# The_Breadboard_Version.net
KiCad netlist of a schematic drawn in EAGLE
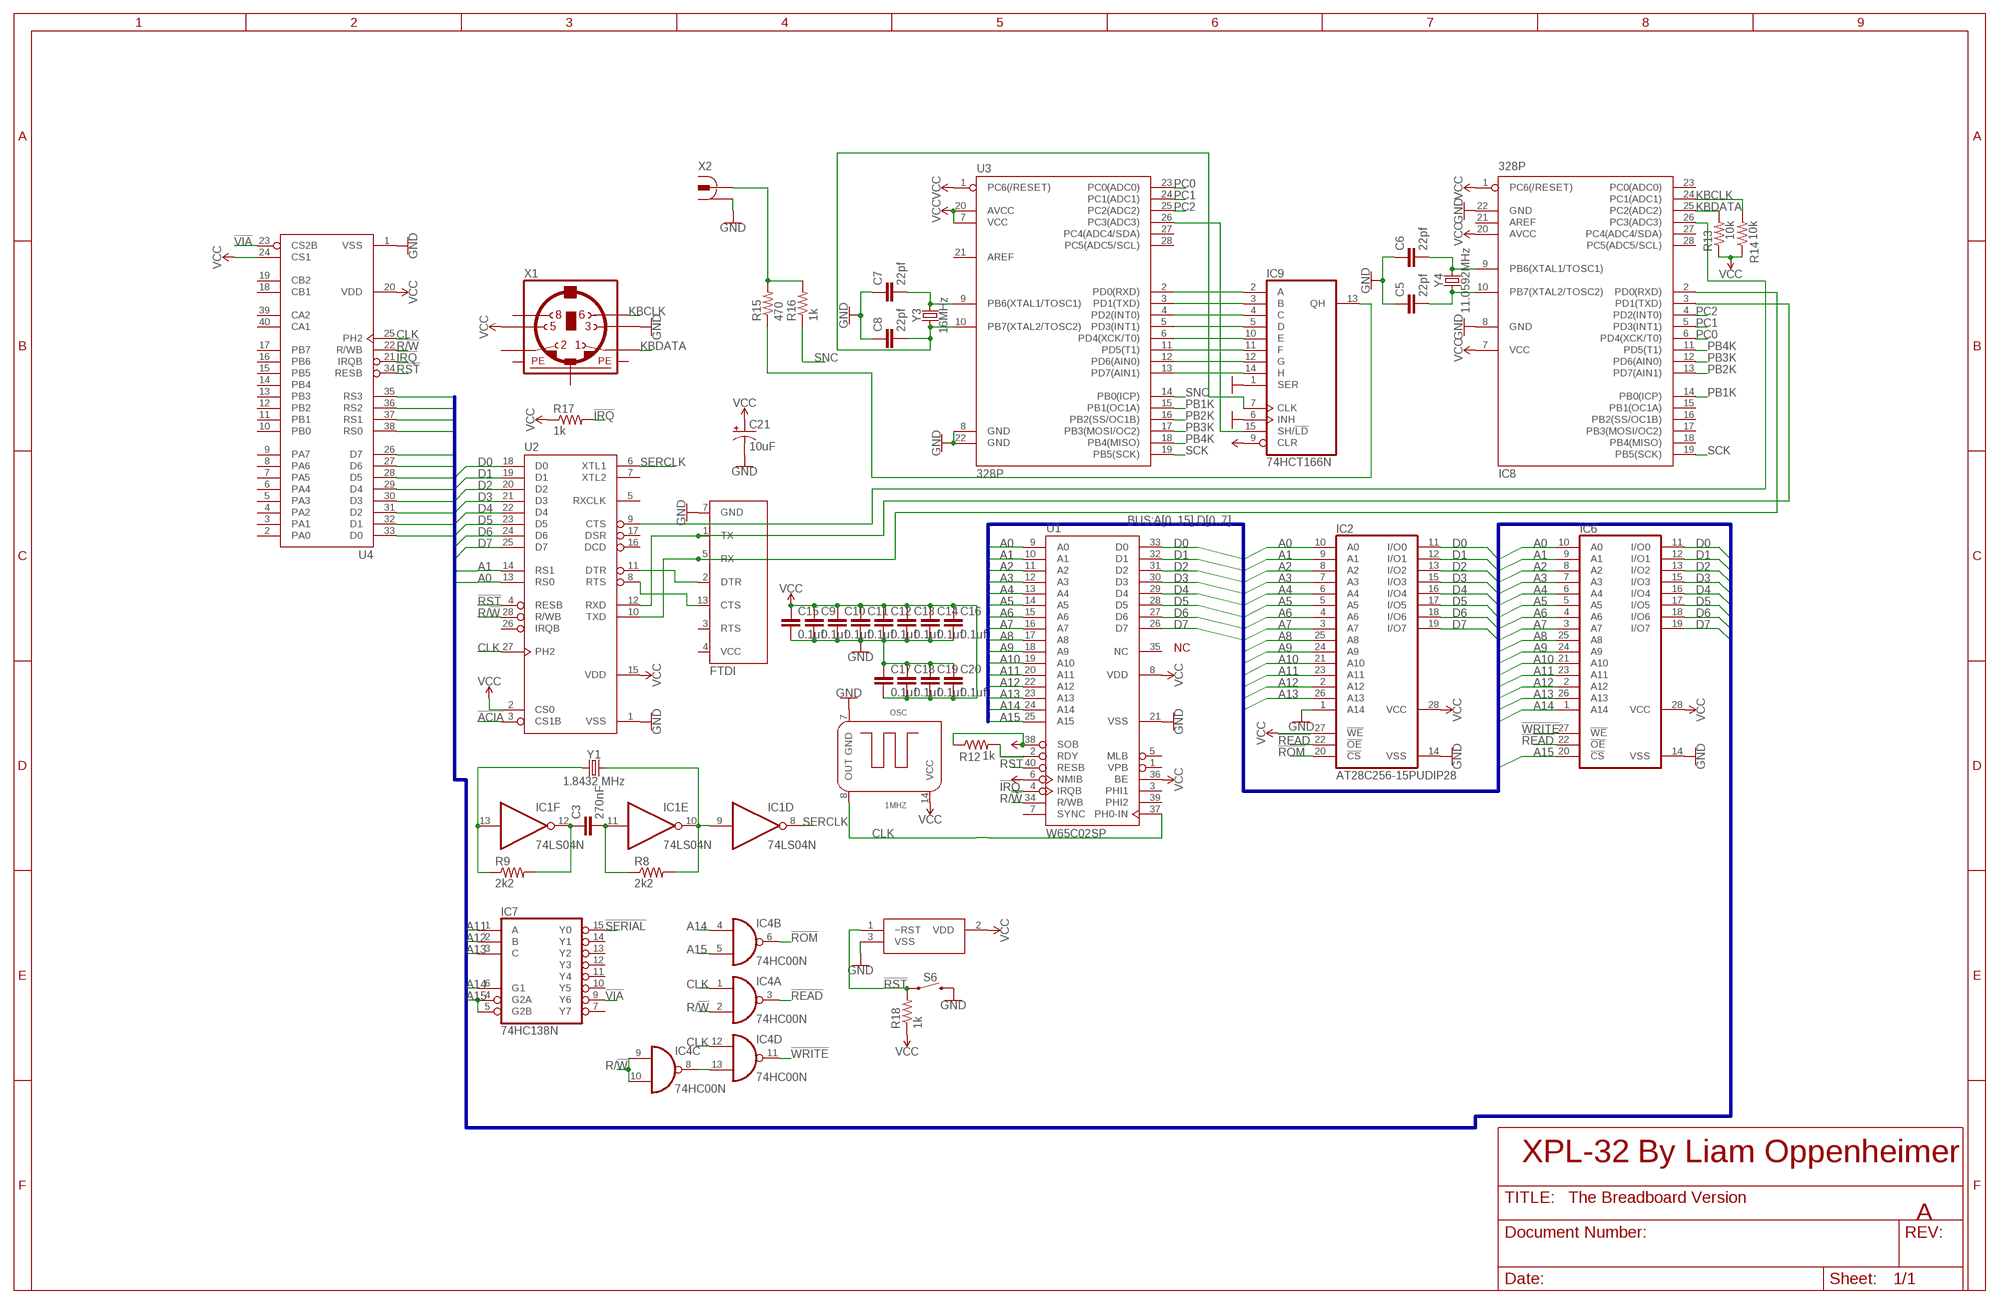
[diagram p0: schematic, sheet 1]

(export (version "E")
  (design (tool "Eeschema 10.0.6"))
  (components
    (comp (ref "1MHZ")
      (value "OSC")
      (footprint "eagle-import:OSCCAN")
      (libsource (lib "eagle-import") (part "OSC"))
    )
    (comp (ref "C3")
      (value "270nF")
      (footprint "eagle-import:C025-025X050")
      (libsource (lib "eagle-import") (part "C-EU025-025X050"))
    )
    (comp (ref "C5")
      (value "22pf")
      (footprint "eagle-import:C025-025X050")
      (libsource (lib "eagle-import") (part "C-EU025-025X050"))
    )
    (comp (ref "C6")
      (value "22pf")
      (footprint "eagle-import:C025-025X050")
      (libsource (lib "eagle-import") (part "C-EU025-025X050"))
    )
    (comp (ref "C7")
      (value "22pf")
      (footprint "eagle-import:C025-025X050")
      (libsource (lib "eagle-import") (part "C-EU025-025X050"))
    )
    (comp (ref "C8")
      (value "22pf")
      (footprint "eagle-import:C025-025X050")
      (libsource (lib "eagle-import") (part "C-EU025-025X050"))
    )
    (comp (ref "C9")
      (value "0.1uf")
      (footprint "eagle-import:C025-025X050")
      (libsource (lib "eagle-import") (part "C-EU025-025X050"))
    )
    (comp (ref "C10")
      (value "0.1uf")
      (footprint "eagle-import:C025-025X050")
      (libsource (lib "eagle-import") (part "C-EU025-025X050"))
    )
    (comp (ref "C11")
      (value "0.1uf")
      (footprint "eagle-import:C025-025X050")
      (libsource (lib "eagle-import") (part "C-EU025-025X050"))
    )
    (comp (ref "C12")
      (value "0.1uf")
      (footprint "eagle-import:C025-025X050")
      (libsource (lib "eagle-import") (part "C-EU025-025X050"))
    )
    (comp (ref "C13")
      (value "0.1uf")
      (footprint "eagle-import:C025-025X050")
      (libsource (lib "eagle-import") (part "C-EU025-025X050"))
    )
    (comp (ref "C14")
      (value "0.1uf")
      (footprint "eagle-import:C025-025X050")
      (libsource (lib "eagle-import") (part "C-EU025-025X050"))
    )
    (comp (ref "C15")
      (value "0.1uf")
      (footprint "eagle-import:C025-025X050")
      (libsource (lib "eagle-import") (part "C-EU025-025X050"))
    )
    (comp (ref "C16")
      (value "0.1uf")
      (footprint "eagle-import:C025-025X050")
      (libsource (lib "eagle-import") (part "C-EU025-025X050"))
    )
    (comp (ref "C17")
      (value "0.1uf")
      (footprint "eagle-import:C025-025X050")
      (libsource (lib "eagle-import") (part "C-EU025-025X050"))
    )
    (comp (ref "C18")
      (value "0.1uf")
      (footprint "eagle-import:C025-025X050")
      (libsource (lib "eagle-import") (part "C-EU025-025X050"))
    )
    (comp (ref "C19")
      (value "0.1uf")
      (footprint "eagle-import:C025-025X050")
      (libsource (lib "eagle-import") (part "C-EU025-025X050"))
    )
    (comp (ref "C20")
      (value "0.1uf")
      (footprint "eagle-import:C025-025X050")
      (libsource (lib "eagle-import") (part "C-EU025-025X050"))
    )
    (comp (ref "C21")
      (value "10uF")
      (footprint "eagle-import:E2,5-7")
      (libsource (lib "eagle-import") (part "CPOL-USE2.5-7"))
    )
    (comp (ref "IC1")
      (value "74LS04N")
      (footprint "eagle-import:DIL14")
      (libsource (lib "eagle-import") (part "7404NLS"))
    )
    (comp (ref "IC2")
      (value "AT28C256-15PUDIP28")
      (footprint "eagle-import:DIP-28")
      (libsource (lib "eagle-import") (part "AT28C256-15PUDIP28"))
    )
    (comp (ref "IC4")
      (value "74HC00N")
      (footprint "eagle-import:DIL14")
      (libsource (lib "eagle-import") (part "7400NHC"))
    )
    (comp (ref "IC6")
      (value "62256P")
      (footprint "eagle-import:DIL28-6")
      (libsource (lib "eagle-import") (part "62256P"))
    )
    (comp (ref "IC7")
      (value "74HC138N")
      (footprint "eagle-import:DIL16")
      (libsource (lib "eagle-import") (part "74138NHC"))
    )
    (comp (ref "IC8")
      (value "328P")
      (footprint "eagle-import:DIL28-3")
      (libsource (lib "eagle-import") (part "MEGA8-P"))
    )
    (comp (ref "IC9")
      (value "74HCT166N")
      (footprint "eagle-import:DIL16")
      (libsource (lib "eagle-import") (part "74166NLS"))
    )
    (comp (ref "IC10")
      (value "MCP120-450DI_TO")
      (footprint "eagle-import:TO127P254X495-3")
      (fields
        (field (name "MANUFACTURER_PART_NUMBER") "MCP120-450DI/TO")
        (field (name "MOUSER_PART_NUMBER") "579-MCP120-450DI/TO")
      )
      (libsource (lib "eagle-import") (part "MCP120-450DI_TO"))
    )
    (comp (ref "R8")
      (value "2k2")
      (footprint "eagle-import:0204_7")
      (libsource (lib "eagle-import") (part "R-US_0204/7"))
    )
    (comp (ref "R9")
      (value "2k2")
      (footprint "eagle-import:0204_7")
      (libsource (lib "eagle-import") (part "R-US_0204/7"))
    )
    (comp (ref "R12")
      (value "1k")
      (footprint "eagle-import:0204_7")
      (libsource (lib "eagle-import") (part "R-US_0204/7"))
    )
    (comp (ref "R13")
      (value "10k")
      (footprint "eagle-import:0204_7")
      (libsource (lib "eagle-import") (part "R-US_0204/7"))
    )
    (comp (ref "R14")
      (value "10k")
      (footprint "eagle-import:0204_7")
      (libsource (lib "eagle-import") (part "R-US_0204/7"))
    )
    (comp (ref "R15")
      (value "470")
      (footprint "eagle-import:0204_7")
      (libsource (lib "eagle-import") (part "R-US_0204/7"))
    )
    (comp (ref "R16")
      (value "1k")
      (footprint "eagle-import:0204_7")
      (libsource (lib "eagle-import") (part "R-US_0204/7"))
    )
    (comp (ref "R17")
      (value "1k")
      (footprint "eagle-import:0204_7")
      (libsource (lib "eagle-import") (part "R-US_0204/7"))
    )
    (comp (ref "R18")
      (value "1k")
      (footprint "eagle-import:0204_7")
      (libsource (lib "eagle-import") (part "R-US_0204/7"))
    )
    (comp (ref "S6")
      (value "MOMENTARY-SWITCH-SPST-PTH-6.0MM")
      (footprint "eagle-import:TACTILE_SWITCH_PTH_6.0MM")
      (libsource (lib "eagle-import") (part "MOMENTARY-SWITCH-SPST-PTH-6.0MM"))
    )
    (comp (ref "U1")
      (value "W65C02SP")
      (footprint "eagle-import:DIP-40")
      (libsource (lib "eagle-import") (part "W65C02SP"))
    )
    (comp (ref "U2")
      (value "G65SC51P")
      (footprint "eagle-import:DIP-28")
      (libsource (lib "eagle-import") (part "G65SC51P"))
    )
    (comp (ref "U3")
      (value "328P")
      (footprint "eagle-import:DIP28")
      (libsource (lib "eagle-import") (part "ATMEGA328P_PDIP"))
    )
    (comp (ref "U4")
      (value "G65SC22P")
      (footprint "eagle-import:DIP-40")
      (libsource (lib "eagle-import") (part "G65SC22P"))
    )
    (comp (ref "U6")
      (value "FTDI")
      (footprint "eagle-import:FTDI")
      (libsource (lib "eagle-import") (part "FTDI"))
    )
    (comp (ref "X1")
      (value "MINI_DIN_6")
      (footprint "eagle-import:M_DIN6")
      (libsource (lib "eagle-import") (part "MINI_DIN_6"))
    )
    (comp (ref "X2")
      (value "736880-49")
      (footprint "eagle-import:736880-49")
      (libsource (lib "eagle-import") (part "736880-49"))
    )
    (comp (ref "Y1")
      (value "1.8432 MHz")
      (footprint "eagle-import:HC49U")
      (libsource (lib "eagle-import") (part "CRYSTALPTH-HC49UV"))
    )
    (comp (ref "Y3")
      (value "16MHz")
      (footprint "eagle-import:HC49U")
      (libsource (lib "eagle-import") (part "CRYSTALPTH-HC49UV"))
    )
    (comp (ref "Y4")
      (value "11.0592MHz")
      (footprint "eagle-import:HC49U")
      (libsource (lib "eagle-import") (part "CRYSTALPTH-HC49UV"))
    )
  )
  (nets
    (net (code "1") (name "/A0") (class "Default")
      (node (ref "IC2") (pin "10") (pinfunction "A0_10") (pintype "input"))
      (node (ref "IC6") (pin "10") (pinfunction "A0_10") (pintype "input"))
      (node (ref "U1") (pin "9") (pinfunction "A0_9") (pintype "bidirectional"))
      (node (ref "U2") (pin "13") (pinfunction "RS0_13") (pintype "input"))
      (node (ref "U4") (pin "38") (pinfunction "RS0_38") (pintype "input"))
    )
    (net (code "2") (name "/A1") (class "Default")
      (node (ref "IC2") (pin "9") (pinfunction "A1_9") (pintype "input"))
      (node (ref "IC6") (pin "9") (pinfunction "A1_9") (pintype "input"))
      (node (ref "U1") (pin "10") (pinfunction "A1_10") (pintype "bidirectional"))
      (node (ref "U2") (pin "14") (pinfunction "RS1_14") (pintype "input"))
      (node (ref "U4") (pin "37") (pinfunction "RS1_37") (pintype "input"))
    )
    (net (code "3") (name "/A2") (class "Default")
      (node (ref "IC2") (pin "8") (pinfunction "A2_8") (pintype "input"))
      (node (ref "IC6") (pin "8") (pinfunction "A2_8") (pintype "input"))
      (node (ref "U1") (pin "11") (pinfunction "A2_11") (pintype "bidirectional"))
      (node (ref "U4") (pin "36") (pinfunction "RS2_36") (pintype "input"))
    )
    (net (code "4") (name "/A3") (class "Default")
      (node (ref "IC2") (pin "7") (pinfunction "A3_7") (pintype "input"))
      (node (ref "IC6") (pin "7") (pinfunction "A3_7") (pintype "input"))
      (node (ref "U1") (pin "12") (pinfunction "A3_12") (pintype "bidirectional"))
      (node (ref "U4") (pin "35") (pinfunction "RS3_35") (pintype "input"))
    )
    (net (code "5") (name "/A4") (class "Default")
      (node (ref "IC2") (pin "6") (pinfunction "A4_6") (pintype "input"))
      (node (ref "IC6") (pin "6") (pinfunction "A4_6") (pintype "input"))
      (node (ref "U1") (pin "13") (pinfunction "A4_13") (pintype "bidirectional"))
    )
    (net (code "6") (name "/A5") (class "Default")
      (node (ref "IC2") (pin "5") (pinfunction "A5_5") (pintype "input"))
      (node (ref "IC6") (pin "5") (pinfunction "A5_5") (pintype "input"))
      (node (ref "U1") (pin "14") (pinfunction "A5_14") (pintype "bidirectional"))
    )
    (net (code "7") (name "/A6") (class "Default")
      (node (ref "IC2") (pin "4") (pinfunction "A6_4") (pintype "input"))
      (node (ref "IC6") (pin "4") (pinfunction "A6_4") (pintype "input"))
      (node (ref "U1") (pin "15") (pinfunction "A6_15") (pintype "bidirectional"))
    )
    (net (code "8") (name "/A7") (class "Default")
      (node (ref "IC2") (pin "3") (pinfunction "A7_3") (pintype "input"))
      (node (ref "IC6") (pin "3") (pinfunction "A7_3") (pintype "input"))
      (node (ref "U1") (pin "16") (pinfunction "A7_16") (pintype "bidirectional"))
    )
    (net (code "9") (name "/A8") (class "Default")
      (node (ref "IC2") (pin "25") (pinfunction "A8_25") (pintype "input"))
      (node (ref "IC6") (pin "25") (pinfunction "A8_25") (pintype "input"))
      (node (ref "U1") (pin "17") (pinfunction "A8_17") (pintype "bidirectional"))
    )
    (net (code "10") (name "/A9") (class "Default")
      (node (ref "IC2") (pin "24") (pinfunction "A9_24") (pintype "input"))
      (node (ref "IC6") (pin "24") (pinfunction "A9_24") (pintype "input"))
      (node (ref "U1") (pin "18") (pinfunction "A9_18") (pintype "bidirectional"))
    )
    (net (code "11") (name "/A10") (class "Default")
      (node (ref "IC2") (pin "21") (pinfunction "A10_21") (pintype "input"))
      (node (ref "IC6") (pin "21") (pinfunction "A10_21") (pintype "input"))
      (node (ref "U1") (pin "19") (pinfunction "A10_19") (pintype "bidirectional"))
    )
    (net (code "12") (name "/A11") (class "Default")
      (node (ref "IC2") (pin "23") (pinfunction "A11_23") (pintype "input"))
      (node (ref "IC6") (pin "23") (pinfunction "A11_23") (pintype "input"))
      (node (ref "IC7") (pin "1") (pinfunction "A_1") (pintype "input"))
      (node (ref "U1") (pin "20") (pinfunction "A11_20") (pintype "bidirectional"))
    )
    (net (code "13") (name "/A12") (class "Default")
      (node (ref "IC2") (pin "2") (pinfunction "A12_2") (pintype "input"))
      (node (ref "IC6") (pin "2") (pinfunction "A12_2") (pintype "input"))
      (node (ref "IC7") (pin "2") (pinfunction "B_2") (pintype "input"))
      (node (ref "U1") (pin "22") (pinfunction "A12_22") (pintype "bidirectional"))
    )
    (net (code "14") (name "/A13") (class "Default")
      (node (ref "IC2") (pin "26") (pinfunction "A13_26") (pintype "input"))
      (node (ref "IC6") (pin "26") (pinfunction "A13_26") (pintype "input"))
      (node (ref "IC7") (pin "3") (pinfunction "C_3") (pintype "input"))
      (node (ref "U1") (pin "23") (pinfunction "A13_23") (pintype "bidirectional"))
    )
    (net (code "15") (name "/A14") (class "Default")
      (node (ref "IC4") (pin "4") (pinfunction "I0_4") (pintype "input"))
      (node (ref "IC6") (pin "1") (pinfunction "A14_1") (pintype "input"))
      (node (ref "IC7") (pin "6") (pinfunction "G1_6") (pintype "input"))
      (node (ref "U1") (pin "24") (pinfunction "A14_24") (pintype "bidirectional"))
    )
    (net (code "16") (name "/A15") (class "Default")
      (node (ref "IC4") (pin "5") (pinfunction "I1_5") (pintype "input"))
      (node (ref "IC6") (pin "20") (pinfunction "~{CS}_20") (pintype "input"))
      (node (ref "IC7") (pin "4") (pinfunction "G2A_4") (pintype "input"))
      (node (ref "IC7") (pin "5") (pinfunction "G2B_5") (pintype "input"))
      (node (ref "U1") (pin "25") (pinfunction "A15_25") (pintype "bidirectional"))
    )
    (net (code "17") (name "/CLK") (class "Default")
      (node (ref "1MHZ") (pin "8") (pinfunction "OUT_8") (pintype "bidirectional"))
      (node (ref "IC4") (pin "1") (pinfunction "I0_1") (pintype "input"))
      (node (ref "IC4") (pin "12") (pinfunction "I0_12") (pintype "input"))
      (node (ref "U1") (pin "37") (pinfunction "PH0-IN_37") (pintype "input"))
      (node (ref "U2") (pin "27") (pinfunction "PH2_27") (pintype "power_in"))
      (node (ref "U4") (pin "25") (pinfunction "PH2_25") (pintype "input"))
    )
    (net (code "18") (name "/D0") (class "Default")
      (node (ref "IC2") (pin "11") (pinfunction "I/O0_11") (pintype "bidirectional"))
      (node (ref "IC6") (pin "11") (pinfunction "I/O0_11") (pintype "bidirectional"))
      (node (ref "U1") (pin "33") (pinfunction "D0_33") (pintype "bidirectional"))
      (node (ref "U2") (pin "18") (pinfunction "D0_18") (pintype "bidirectional"))
      (node (ref "U4") (pin "33") (pinfunction "D0_33") (pintype "bidirectional"))
    )
    (net (code "19") (name "/D1") (class "Default")
      (node (ref "IC2") (pin "12") (pinfunction "I/O1_12") (pintype "bidirectional"))
      (node (ref "IC6") (pin "12") (pinfunction "I/O1_12") (pintype "bidirectional"))
      (node (ref "U1") (pin "32") (pinfunction "D1_32") (pintype "bidirectional"))
      (node (ref "U2") (pin "19") (pinfunction "D1_19") (pintype "bidirectional"))
      (node (ref "U4") (pin "32") (pinfunction "D1_32") (pintype "bidirectional"))
    )
    (net (code "20") (name "/D2") (class "Default")
      (node (ref "IC2") (pin "13") (pinfunction "I/O2_13") (pintype "bidirectional"))
      (node (ref "IC6") (pin "13") (pinfunction "I/O2_13") (pintype "bidirectional"))
      (node (ref "U1") (pin "31") (pinfunction "D2_31") (pintype "bidirectional"))
      (node (ref "U2") (pin "20") (pinfunction "D2_20") (pintype "bidirectional"))
      (node (ref "U4") (pin "31") (pinfunction "D2_31") (pintype "bidirectional"))
    )
    (net (code "21") (name "/D3") (class "Default")
      (node (ref "IC2") (pin "15") (pinfunction "I/O3_15") (pintype "bidirectional"))
      (node (ref "IC6") (pin "15") (pinfunction "I/O3_15") (pintype "bidirectional"))
      (node (ref "U1") (pin "30") (pinfunction "D3_30") (pintype "bidirectional"))
      (node (ref "U2") (pin "21") (pinfunction "D3_21") (pintype "bidirectional"))
      (node (ref "U4") (pin "30") (pinfunction "D3_30") (pintype "bidirectional"))
    )
    (net (code "22") (name "/D4") (class "Default")
      (node (ref "IC2") (pin "16") (pinfunction "I/O4_16") (pintype "bidirectional"))
      (node (ref "IC6") (pin "16") (pinfunction "I/O4_16") (pintype "bidirectional"))
      (node (ref "U1") (pin "29") (pinfunction "D4_29") (pintype "bidirectional"))
      (node (ref "U2") (pin "22") (pinfunction "D4_22") (pintype "bidirectional"))
      (node (ref "U4") (pin "29") (pinfunction "D4_29") (pintype "bidirectional"))
    )
    (net (code "23") (name "/D5") (class "Default")
      (node (ref "IC2") (pin "17") (pinfunction "I/O5_17") (pintype "bidirectional"))
      (node (ref "IC6") (pin "17") (pinfunction "I/O5_17") (pintype "bidirectional"))
      (node (ref "U1") (pin "28") (pinfunction "D5_28") (pintype "bidirectional"))
      (node (ref "U2") (pin "23") (pinfunction "D5_23") (pintype "bidirectional"))
      (node (ref "U4") (pin "28") (pinfunction "D5_28") (pintype "bidirectional"))
    )
    (net (code "24") (name "/D6") (class "Default")
      (node (ref "IC2") (pin "18") (pinfunction "I/O6_18") (pintype "bidirectional"))
      (node (ref "IC6") (pin "18") (pinfunction "I/O6_18") (pintype "bidirectional"))
      (node (ref "U1") (pin "27") (pinfunction "D6_27") (pintype "bidirectional"))
      (node (ref "U2") (pin "24") (pinfunction "D6_24") (pintype "bidirectional"))
      (node (ref "U4") (pin "27") (pinfunction "D6_27") (pintype "bidirectional"))
    )
    (net (code "25") (name "/D7") (class "Default")
      (node (ref "IC2") (pin "19") (pinfunction "I/O7_19") (pintype "bidirectional"))
      (node (ref "IC6") (pin "19") (pinfunction "I/O7_19") (pintype "bidirectional"))
      (node (ref "U1") (pin "26") (pinfunction "D7_26") (pintype "bidirectional"))
      (node (ref "U2") (pin "25") (pinfunction "D7_25") (pintype "bidirectional"))
      (node (ref "U4") (pin "26") (pinfunction "D7_26") (pintype "bidirectional"))
    )
    (net (code "26") (name "/KBCLK") (class "Default")
      (node (ref "IC8") (pin "24") (pinfunction "PC1(ADC1)_24") (pintype "bidirectional"))
      (node (ref "R14") (pin "2") (pinfunction "2_2") (pintype "passive"))
      (node (ref "X1") (pin "6") (pinfunction "6_6") (pintype "passive"))
    )
    (net (code "27") (name "/KBDATA") (class "Default")
      (node (ref "IC8") (pin "25") (pinfunction "PC2(ADC2)_25") (pintype "bidirectional"))
      (node (ref "R13") (pin "2") (pinfunction "2_2") (pintype "passive"))
      (node (ref "X1") (pin "1") (pinfunction "1_1") (pintype "passive"))
    )
    (net (code "28") (name "/PB1K") (class "Default")
      (node (ref "IC8") (pin "14") (pinfunction "PB0(ICP)_14") (pintype "bidirectional"))
      (node (ref "U3") (pin "15") (pinfunction "PB1(OC1A)_15") (pintype "bidirectional"))
    )
    (net (code "29") (name "/PB2K") (class "Default")
      (node (ref "IC8") (pin "13") (pinfunction "PD7(AIN1)_13") (pintype "bidirectional"))
      (node (ref "U3") (pin "16") (pinfunction "PB2(SS/OC1B)_16") (pintype "bidirectional"))
    )
    (net (code "30") (name "/PB3K") (class "Default")
      (node (ref "IC8") (pin "12") (pinfunction "PD6(AIN0)_12") (pintype "bidirectional"))
      (node (ref "U3") (pin "17") (pinfunction "PB3(MOSI/OC2)_17") (pintype "bidirectional"))
    )
    (net (code "31") (name "/PB4K") (class "Default")
      (node (ref "IC8") (pin "11") (pinfunction "PD5(T1)_11") (pintype "bidirectional"))
      (node (ref "U3") (pin "18") (pinfunction "PB4(MISO)_18") (pintype "bidirectional"))
    )
    (net (code "32") (name "/PC0") (class "Default")
      (node (ref "IC8") (pin "6") (pinfunction "PD4(XCK/T0)_6") (pintype "bidirectional"))
      (node (ref "U3") (pin "23") (pinfunction "PC0(ADC0)_23") (pintype "bidirectional"))
    )
    (net (code "33") (name "/PC1") (class "Default")
      (node (ref "IC8") (pin "5") (pinfunction "PD3(INT1)_5") (pintype "bidirectional"))
      (node (ref "U3") (pin "24") (pinfunction "PC1(ADC1)_24") (pintype "bidirectional"))
    )
    (net (code "34") (name "/PC2") (class "Default")
      (node (ref "IC8") (pin "4") (pinfunction "PD2(INT0)_4") (pintype "bidirectional"))
      (node (ref "U3") (pin "25") (pinfunction "PC2(ADC2)_25") (pintype "bidirectional"))
    )
    (net (code "35") (name "/PE1") (class "Default")
      (node (ref "X1") (pin "SH1") (pinfunction "PE1_SH1") (pintype "power_in"))
    )
    (net (code "36") (name "/PE2") (class "Default")
      (node (ref "X1") (pin "SH2") (pinfunction "PE2_SH2") (pintype "power_in"))
    )
    (net (code "37") (name "/PE3") (class "Default")
      (node (ref "X1") (pin "SH3") (pinfunction "PE3_SH3") (pintype "power_in"))
    )
    (net (code "38") (name "/R{slash}~{W}") (class "Default")
      (node (ref "IC4") (pin "10") (pinfunction "I1_10") (pintype "input"))
      (node (ref "IC4") (pin "2") (pinfunction "I1_2") (pintype "input"))
      (node (ref "IC4") (pin "9") (pinfunction "I0_9") (pintype "input"))
      (node (ref "U1") (pin "34") (pinfunction "R/WB_34") (pintype "output"))
      (node (ref "U2") (pin "28") (pinfunction "R/WB_28") (pintype "input"))
      (node (ref "U4") (pin "22") (pinfunction "R/WB_22") (pintype "input"))
    )
    (net (code "39") (name "/SCK") (class "Default")
      (node (ref "IC8") (pin "19") (pinfunction "PB5(SCK)_19") (pintype "bidirectional"))
      (node (ref "U3") (pin "19") (pinfunction "PB5(SCK)_19") (pintype "bidirectional"))
    )
    (net (code "40") (name "/SERCLK") (class "Default")
      (node (ref "IC1") (pin "8") (pinfunction "O_8") (pintype "output"))
      (node (ref "U2") (pin "6") (pinfunction "XTL1_6") (pintype "input"))
    )
    (net (code "41") (name "/SNC") (class "Default")
      (node (ref "R16") (pin "1") (pinfunction "1_1") (pintype "passive"))
      (node (ref "U3") (pin "14") (pinfunction "PB0(ICP)_14") (pintype "bidirectional"))
    )
    (net (code "43") (name "/~{ACIA}") (class "Default")
      (node (ref "U2") (pin "3") (pinfunction "CS1B_3") (pintype "input"))
    )
    (net (code "44") (name "/~{IRQ}") (class "Default")
      (node (ref "R17") (pin "2") (pinfunction "2_2") (pintype "passive"))
      (node (ref "U1") (pin "4") (pinfunction "IRQB_4") (pintype "input"))
      (node (ref "U4") (pin "21") (pinfunction "IRQB_21") (pintype "output"))
    )
    (net (code "45") (name "/~{READ}") (class "Default")
      (node (ref "IC2") (pin "22") (pinfunction "~{OE}_22") (pintype "input"))
      (node (ref "IC4") (pin "3") (pinfunction "O_3") (pintype "output"))
      (node (ref "IC6") (pin "22") (pinfunction "~{OE}_22") (pintype "input"))
    )
    (net (code "46") (name "/~{ROM}") (class "Default")
      (node (ref "IC2") (pin "20") (pinfunction "~{CS}_20") (pintype "input"))
      (node (ref "IC4") (pin "6") (pinfunction "O_6") (pintype "output"))
    )
    (net (code "47") (name "/~{RST}") (class "Default")
      (node (ref "IC10") (pin "1") (pinfunction "~{RST}_1") (pintype "bidirectional"))
      (node (ref "R18") (pin "2") (pinfunction "2_2") (pintype "passive"))
      (node (ref "S6") (pin "1") (pinfunction "1_1") (pintype "passive"))
      (node (ref "U1") (pin "40") (pinfunction "RESB_40") (pintype "input"))
      (node (ref "U2") (pin "4") (pinfunction "RESB_4") (pintype "input"))
      (node (ref "U4") (pin "34") (pinfunction "RESB_34") (pintype "input"))
    )
    (net (code "48") (name "/~{SERIAL}") (class "Default")
      (node (ref "IC7") (pin "15") (pinfunction "Y0_15") (pintype "output"))
    )
    (net (code "49") (name "/~{VIA}") (class "Default")
      (node (ref "IC7") (pin "9") (pinfunction "Y6_9") (pintype "output"))
      (node (ref "U4") (pin "23") (pinfunction "CS2B_23") (pintype "input"))
    )
    (net (code "50") (name "/~{WRITE}") (class "Default")
      (node (ref "IC4") (pin "11") (pinfunction "O_11") (pintype "output"))
      (node (ref "IC6") (pin "27") (pinfunction "~{WE}_27") (pintype "input"))
    )
    (net (code "51") (name "GND") (class "Default")
      (node (ref "1MHZ") (pin "7") (pinfunction "GND_7") (pintype "bidirectional"))
      (node (ref "C10") (pin "2") (pinfunction "2_2") (pintype "passive"))
      (node (ref "C11") (pin "2") (pinfunction "2_2") (pintype "passive"))
      (node (ref "C12") (pin "2") (pinfunction "2_2") (pintype "passive"))
      (node (ref "C13") (pin "2") (pinfunction "2_2") (pintype "passive"))
      (node (ref "C14") (pin "2") (pinfunction "2_2") (pintype "passive"))
      (node (ref "C15") (pin "2") (pinfunction "2_2") (pintype "passive"))
      (node (ref "C16") (pin "2") (pinfunction "2_2") (pintype "passive"))
      (node (ref "C17") (pin "1") (pinfunction "1_1") (pintype "passive"))
      (node (ref "C18") (pin "1") (pinfunction "1_1") (pintype "passive"))
      (node (ref "C19") (pin "1") (pinfunction "1_1") (pintype "passive"))
      (node (ref "C20") (pin "1") (pinfunction "1_1") (pintype "passive"))
      (node (ref "C21") (pin "-") (pinfunction "-_-") (pintype "passive"))
      (node (ref "C5") (pin "1") (pinfunction "1_1") (pintype "passive"))
      (node (ref "C6") (pin "1") (pinfunction "1_1") (pintype "passive"))
      (node (ref "C7") (pin "1") (pinfunction "1_1") (pintype "passive"))
      (node (ref "C8") (pin "1") (pinfunction "1_1") (pintype "passive"))
      (node (ref "C9") (pin "2") (pinfunction "2_2") (pintype "passive"))
      (node (ref "IC10") (pin "3") (pinfunction "VSS_3") (pintype "bidirectional"))
      (node (ref "IC2") (pin "1") (pinfunction "A14_1") (pintype "input"))
      (node (ref "IC2") (pin "14") (pinfunction "VSS_14") (pintype "power_in"))
      (node (ref "IC6") (pin "14") (pinfunction "VSS_14") (pintype "power_in"))
      (node (ref "IC8") (pin "22") (pinfunction "GND_22") (pintype "power_in"))
      (node (ref "IC8") (pin "8") (pinfunction "GND_8") (pintype "power_in"))
      (node (ref "IC9") (pin "1") (pinfunction "SER_1") (pintype "input"))
      (node (ref "IC9") (pin "6") (pinfunction "INH_6") (pintype "input"))
      (node (ref "S6") (pin "3") (pinfunction "2_3") (pintype "passive"))
      (node (ref "U1") (pin "21") (pinfunction "VSS_21") (pintype "power_in"))
      (node (ref "U2") (pin "1") (pinfunction "VSS_1") (pintype "power_in"))
      (node (ref "U3") (pin "22") (pinfunction "GND_22") (pintype "bidirectional"))
      (node (ref "U3") (pin "8") (pinfunction "GND_8") (pintype "bidirectional"))
      (node (ref "U4") (pin "1") (pinfunction "VSS_1") (pintype "power_in"))
      (node (ref "U6") (pin "7") (pinfunction "GND_7") (pintype "bidirectional"))
      (node (ref "X1") (pin "3") (pinfunction "3_3") (pintype "passive"))
      (node (ref "X2") (pin "1") (pinfunction "1_1") (pintype "passive"))
      (node (ref "X2") (pin "1@1") (pinfunction "1_1@1") (pintype "passive"))
      (node (ref "X2") (pin "1@2") (pinfunction "1_1@2") (pintype "passive"))
    )
    (net (code "52") (name "Net-(IC1D-I)") (class "Default")
      (node (ref "IC1") (pin "10") (pinfunction "O_10") (pintype "output"))
      (node (ref "IC1") (pin "9") (pinfunction "I_9") (pintype "input"))
      (node (ref "R8") (pin "2") (pinfunction "2_2") (pintype "passive"))
      (node (ref "Y1") (pin "2") (pinfunction "2_2") (pintype "passive"))
    )
    (net (code "53") (name "Net-(IC1E-I)") (class "Default")
      (node (ref "C3") (pin "2") (pinfunction "2_2") (pintype "passive"))
      (node (ref "IC1") (pin "11") (pinfunction "I_11") (pintype "input"))
      (node (ref "R8") (pin "1") (pinfunction "1_1") (pintype "passive"))
    )
    (net (code "54") (name "Net-(IC1F-I)") (class "Default")
      (node (ref "IC1") (pin "13") (pinfunction "I_13") (pintype "input"))
      (node (ref "R9") (pin "1") (pinfunction "1_1") (pintype "passive"))
      (node (ref "Y1") (pin "1") (pinfunction "1_1") (pintype "passive"))
    )
    (net (code "55") (name "Net-(IC1F-O)") (class "Default")
      (node (ref "C3") (pin "1") (pinfunction "1_1") (pintype "passive"))
      (node (ref "IC1") (pin "12") (pinfunction "O_12") (pintype "output"))
      (node (ref "R9") (pin "2") (pinfunction "2_2") (pintype "passive"))
    )
    (net (code "56") (name "Net-(IC4C-O)") (class "Default")
      (node (ref "IC4") (pin "13") (pinfunction "I1_13") (pintype "input"))
      (node (ref "IC4") (pin "8") (pinfunction "O_8") (pintype "output"))
    )
    (net (code "57") (name "Net-(IC8-PB6(XTAL1{slash}TOSC1))") (class "Default")
      (node (ref "C6") (pin "2") (pinfunction "2_2") (pintype "passive"))
      (node (ref "IC8") (pin "9") (pinfunction "PB6(XTAL1/TOSC1)_9") (pintype "bidirectional"))
      (node (ref "Y4") (pin "2") (pinfunction "2_2") (pintype "passive"))
    )
    (net (code "58") (name "Net-(IC8-PB7(XTAL2{slash}TOSC2))") (class "Default")
      (node (ref "C5") (pin "2") (pinfunction "2_2") (pintype "passive"))
      (node (ref "IC8") (pin "10") (pinfunction "PB7(XTAL2/TOSC2)_10") (pintype "bidirectional"))
      (node (ref "Y4") (pin "1") (pinfunction "1_1") (pintype "passive"))
    )
    (net (code "59") (name "Net-(IC8-PC3(ADC3))") (class "Default")
      (node (ref "IC8") (pin "26") (pinfunction "PC3(ADC3)_26") (pintype "bidirectional"))
      (node (ref "U2") (pin "9") (pinfunction "CTS_9") (pintype "input"))
    )
    (net (code "60") (name "Net-(IC8-PD0(RXD))") (class "Default")
      (node (ref "IC8") (pin "2") (pinfunction "PD0(RXD)_2") (pintype "bidirectional"))
      (node (ref "U2") (pin "10") (pinfunction "TXD_10") (pintype "output"))
      (node (ref "U6") (pin "5") (pinfunction "RX_5") (pintype "bidirectional"))
    )
    (net (code "61") (name "Net-(IC8-PD1(TXD))") (class "Default")
      (node (ref "IC8") (pin "3") (pinfunction "PD1(TXD)_3") (pintype "bidirectional"))
      (node (ref "U2") (pin "12") (pinfunction "RXD_12") (pintype "input"))
      (node (ref "U6") (pin "1") (pinfunction "TX_1") (pintype "bidirectional"))
    )
    (net (code "62") (name "Net-(IC9A-A)") (class "Default")
      (node (ref "IC9") (pin "2") (pinfunction "A_2") (pintype "input"))
      (node (ref "U3") (pin "2") (pinfunction "PD0(RXD)_2") (pintype "bidirectional"))
    )
    (net (code "63") (name "Net-(IC9A-B)") (class "Default")
      (node (ref "IC9") (pin "3") (pinfunction "B_3") (pintype "input"))
      (node (ref "U3") (pin "3") (pinfunction "PD1(TXD)_3") (pintype "bidirectional"))
    )
    (net (code "64") (name "Net-(IC9A-C)") (class "Default")
      (node (ref "IC9") (pin "4") (pinfunction "C_4") (pintype "input"))
      (node (ref "U3") (pin "4") (pinfunction "PD2(INT0)_4") (pintype "bidirectional"))
    )
    (net (code "65") (name "Net-(IC9A-CLK)") (class "Default")
      (node (ref "C8") (pin "2") (pinfunction "2_2") (pintype "passive"))
      (node (ref "IC9") (pin "7") (pinfunction "CLK_7") (pintype "input"))
      (node (ref "U3") (pin "10") (pinfunction "PB7(XTAL2/TOSC2)_10") (pintype "bidirectional"))
      (node (ref "Y3") (pin "1") (pinfunction "1_1") (pintype "passive"))
    )
    (net (code "66") (name "Net-(IC9A-D)") (class "Default")
      (node (ref "IC9") (pin "5") (pinfunction "D_5") (pintype "input"))
      (node (ref "U3") (pin "5") (pinfunction "PD3(INT1)_5") (pintype "bidirectional"))
    )
    (net (code "67") (name "Net-(IC9A-E)") (class "Default")
      (node (ref "IC9") (pin "10") (pinfunction "E_10") (pintype "input"))
      (node (ref "U3") (pin "6") (pinfunction "PD4(XCK/T0)_6") (pintype "bidirectional"))
    )
    (net (code "68") (name "Net-(IC9A-F)") (class "Default")
      (node (ref "IC9") (pin "11") (pinfunction "F_11") (pintype "input"))
      (node (ref "U3") (pin "11") (pinfunction "PD5(T1)_11") (pintype "bidirectional"))
    )
    (net (code "69") (name "Net-(IC9A-G)") (class "Default")
      (node (ref "IC9") (pin "12") (pinfunction "G_12") (pintype "input"))
      (node (ref "U3") (pin "12") (pinfunction "PD6(AIN0)_12") (pintype "bidirectional"))
    )
    (net (code "70") (name "Net-(IC9A-H)") (class "Default")
      (node (ref "IC9") (pin "14") (pinfunction "H_14") (pintype "input"))
      (node (ref "U3") (pin "13") (pinfunction "PD7(AIN1)_13") (pintype "bidirectional"))
    )
    (net (code "71") (name "Net-(IC9A-QH)") (class "Default")
      (node (ref "IC9") (pin "13") (pinfunction "QH_13") (pintype "output"))
      (node (ref "R15") (pin "1") (pinfunction "1_1") (pintype "passive"))
    )
    (net (code "72") (name "Net-(IC9A-SH{slash}~{LD})") (class "Default")
      (node (ref "IC9") (pin "15") (pinfunction "SH/~{LD}_15") (pintype "input"))
      (node (ref "U3") (pin "26") (pinfunction "PC3(ADC3)_26") (pintype "bidirectional"))
    )
    (net (code "73") (name "Net-(R15-Pad2)") (class "Default")
      (node (ref "R15") (pin "2") (pinfunction "2_2") (pintype "passive"))
      (node (ref "R16") (pin "2") (pinfunction "2_2") (pintype "passive"))
      (node (ref "X2") (pin "2") (pinfunction "2_2") (pintype "passive"))
    )
    (net (code "74") (name "Net-(U1-RDY)") (class "Default")
      (node (ref "R12") (pin "2") (pinfunction "2_2") (pintype "passive"))
      (node (ref "U1") (pin "2") (pinfunction "RDY_2") (pintype "bidirectional"))
    )
    (net (code "75") (name "Net-(U2-DTR)") (class "Default")
      (node (ref "U2") (pin "11") (pinfunction "DTR_11") (pintype "output"))
      (node (ref "U6") (pin "2") (pinfunction "DTR_2") (pintype "bidirectional"))
    )
    (net (code "76") (name "Net-(U2-RTS)") (class "Default")
      (node (ref "U2") (pin "8") (pinfunction "RTS_8") (pintype "output"))
      (node (ref "U6") (pin "13") (pinfunction "CTS_13") (pintype "bidirectional"))
    )
    (net (code "77") (name "Net-(U3-PB6(XTAL1{slash}TOSC1))") (class "Default")
      (node (ref "C7") (pin "2") (pinfunction "2_2") (pintype "passive"))
      (node (ref "U3") (pin "9") (pinfunction "PB6(XTAL1/TOSC1)_9") (pintype "bidirectional"))
      (node (ref "Y3") (pin "2") (pinfunction "2_2") (pintype "passive"))
    )
    (net (code "78") (name "VCC") (class "Default")
      (node (ref "1MHZ") (pin "14") (pinfunction "VCC_14") (pintype "bidirectional"))
      (node (ref "C10") (pin "1") (pinfunction "1_1") (pintype "passive"))
      (node (ref "C11") (pin "1") (pinfunction "1_1") (pintype "passive"))
      (node (ref "C12") (pin "1") (pinfunction "1_1") (pintype "passive"))
      (node (ref "C13") (pin "1") (pinfunction "1_1") (pintype "passive"))
      (node (ref "C14") (pin "1") (pinfunction "1_1") (pintype "passive"))
      (node (ref "C15") (pin "1") (pinfunction "1_1") (pintype "passive"))
      (node (ref "C16") (pin "1") (pinfunction "1_1") (pintype "passive"))
      (node (ref "C17") (pin "2") (pinfunction "2_2") (pintype "passive"))
      (node (ref "C18") (pin "2") (pinfunction "2_2") (pintype "passive"))
      (node (ref "C19") (pin "2") (pinfunction "2_2") (pintype "passive"))
      (node (ref "C20") (pin "2") (pinfunction "2_2") (pintype "passive"))
      (node (ref "C21") (pin "+") (pinfunction "+_+") (pintype "passive"))
      (node (ref "C9") (pin "1") (pinfunction "1_1") (pintype "passive"))
      (node (ref "IC10") (pin "2") (pinfunction "VDD_2") (pintype "bidirectional"))
      (node (ref "IC2") (pin "27") (pinfunction "~{WE}_27") (pintype "input"))
      (node (ref "IC2") (pin "28") (pinfunction "VCC_28") (pintype "power_in"))
      (node (ref "IC6") (pin "28") (pinfunction "VCC_28") (pintype "power_in"))
      (node (ref "IC8") (pin "1") (pinfunction "PC6(/RESET)_1") (pintype "bidirectional"))
      (node (ref "IC8") (pin "20") (pinfunction "AVCC_20") (pintype "power_in"))
      (node (ref "IC8") (pin "7") (pinfunction "VCC_7") (pintype "power_in"))
      (node (ref "IC9") (pin "9") (pinfunction "CLR_9") (pintype "input"))
      (node (ref "R12") (pin "1") (pinfunction "1_1") (pintype "passive"))
      (node (ref "R13") (pin "1") (pinfunction "1_1") (pintype "passive"))
      (node (ref "R14") (pin "1") (pinfunction "1_1") (pintype "passive"))
      (node (ref "R17") (pin "1") (pinfunction "1_1") (pintype "passive"))
      (node (ref "R18") (pin "1") (pinfunction "1_1") (pintype "passive"))
      (node (ref "U1") (pin "36") (pinfunction "BE_36") (pintype "input"))
      (node (ref "U1") (pin "38") (pinfunction "SOB_38") (pintype "input"))
      (node (ref "U1") (pin "6") (pinfunction "NMIB_6") (pintype "input"))
      (node (ref "U1") (pin "8") (pinfunction "VDD_8") (pintype "power_in"))
      (node (ref "U2") (pin "15") (pinfunction "VDD_15") (pintype "power_in"))
      (node (ref "U2") (pin "2") (pinfunction "CS0_2") (pintype "input"))
      (node (ref "U3") (pin "1") (pinfunction "PC6(/RESET)_1") (pintype "bidirectional"))
      (node (ref "U3") (pin "20") (pinfunction "AVCC_20") (pintype "bidirectional"))
      (node (ref "U3") (pin "7") (pinfunction "VCC_7") (pintype "bidirectional"))
      (node (ref "U4") (pin "20") (pinfunction "VDD_20") (pintype "power_in"))
      (node (ref "U4") (pin "24") (pinfunction "CS1_24") (pintype "input"))
      (node (ref "X1") (pin "5") (pinfunction "5_5") (pintype "passive"))
    )
    (net (code "79") (name "unconnected-(IC7A-Y1-Pad14)") (class "Default")
      (node (ref "IC7") (pin "14") (pinfunction "Y1_14") (pintype "output"))
    )
    (net (code "80") (name "unconnected-(IC7A-Y2-Pad13)") (class "Default")
      (node (ref "IC7") (pin "13") (pinfunction "Y2_13") (pintype "output"))
    )
    (net (code "81") (name "unconnected-(IC7A-Y3-Pad12)") (class "Default")
      (node (ref "IC7") (pin "12") (pinfunction "Y3_12") (pintype "output"))
    )
    (net (code "82") (name "unconnected-(IC7A-Y4-Pad11)") (class "Default")
      (node (ref "IC7") (pin "11") (pinfunction "Y4_11") (pintype "output"))
    )
    (net (code "83") (name "unconnected-(IC7A-Y5-Pad10)") (class "Default")
      (node (ref "IC7") (pin "10") (pinfunction "Y5_10") (pintype "output"))
    )
    (net (code "84") (name "unconnected-(IC7A-Y7-Pad7)") (class "Default")
      (node (ref "IC7") (pin "7") (pinfunction "Y7_7") (pintype "output"))
    )
    (net (code "85") (name "unconnected-(IC8-AREF-Pad21)") (class "Default")
      (node (ref "IC8") (pin "21") (pinfunction "AREF_21") (pintype "passive"))
    )
    (net (code "86") (name "unconnected-(IC8-PB1(OC1A)-Pad15)") (class "Default")
      (node (ref "IC8") (pin "15") (pinfunction "PB1(OC1A)_15") (pintype "bidirectional"))
    )
    (net (code "87") (name "unconnected-(IC8-PB2(SS{slash}OC1B)-Pad16)") (class "Default")
      (node (ref "IC8") (pin "16") (pinfunction "PB2(SS/OC1B)_16") (pintype "bidirectional"))
    )
    (net (code "88") (name "unconnected-(IC8-PB3(MOSI{slash}OC2)-Pad17)") (class "Default")
      (node (ref "IC8") (pin "17") (pinfunction "PB3(MOSI/OC2)_17") (pintype "bidirectional"))
    )
    (net (code "89") (name "unconnected-(IC8-PB4(MISO)-Pad18)") (class "Default")
      (node (ref "IC8") (pin "18") (pinfunction "PB4(MISO)_18") (pintype "bidirectional"))
    )
    (net (code "90") (name "unconnected-(IC8-PC0(ADC0)-Pad23)") (class "Default")
      (node (ref "IC8") (pin "23") (pinfunction "PC0(ADC0)_23") (pintype "bidirectional"))
    )
    (net (code "91") (name "unconnected-(IC8-PC4(ADC4{slash}SDA)-Pad27)") (class "Default")
      (node (ref "IC8") (pin "27") (pinfunction "PC4(ADC4/SDA)_27") (pintype "bidirectional"))
    )
    (net (code "92") (name "unconnected-(IC8-PC5(ADC5{slash}SCL)-Pad28)") (class "Default")
      (node (ref "IC8") (pin "28") (pinfunction "PC5(ADC5/SCL)_28") (pintype "bidirectional"))
    )
    (net (code "93") (name "unconnected-(U1-MLB-Pad5)") (class "Default")
      (node (ref "U1") (pin "5") (pinfunction "MLB_5") (pintype "output"))
    )
    (net (code "94") (name "unconnected-(U1-NC-Pad35)") (class "Default")
      (node (ref "U1") (pin "35") (pinfunction "NC_35") (pintype "no_connect"))
    )
    (net (code "95") (name "unconnected-(U1-PHI1-Pad3)") (class "Default")
      (node (ref "U1") (pin "3") (pinfunction "PHI1_3") (pintype "output"))
    )
    (net (code "96") (name "unconnected-(U1-PHI2-Pad39)") (class "Default")
      (node (ref "U1") (pin "39") (pinfunction "PHI2_39") (pintype "output"))
    )
    (net (code "97") (name "unconnected-(U1-SYNC-Pad7)") (class "Default")
      (node (ref "U1") (pin "7") (pinfunction "SYNC_7") (pintype "output"))
    )
    (net (code "98") (name "unconnected-(U1-VPB-Pad1)") (class "Default")
      (node (ref "U1") (pin "1") (pinfunction "VPB_1") (pintype "output"))
    )
    (net (code "99") (name "unconnected-(U2-DCD-Pad16)") (class "Default")
      (node (ref "U2") (pin "16") (pinfunction "DCD_16") (pintype "input"))
    )
    (net (code "100") (name "unconnected-(U2-DSR-Pad17)") (class "Default")
      (node (ref "U2") (pin "17") (pinfunction "DSR_17") (pintype "input"))
    )
    (net (code "101") (name "unconnected-(U2-IRQB-Pad26)") (class "Default")
      (node (ref "U2") (pin "26") (pinfunction "IRQB_26") (pintype "output"))
    )
    (net (code "102") (name "unconnected-(U2-RXCLK-Pad5)") (class "Default")
      (node (ref "U2") (pin "5") (pinfunction "RXCLK_5") (pintype "bidirectional"))
    )
    (net (code "103") (name "unconnected-(U2-XTL2-Pad7)") (class "Default")
      (node (ref "U2") (pin "7") (pinfunction "XTL2_7") (pintype "output"))
    )
    (net (code "104") (name "unconnected-(U3-AREF-Pad21)") (class "Default")
      (node (ref "U3") (pin "21") (pinfunction "AREF_21") (pintype "bidirectional"))
    )
    (net (code "105") (name "unconnected-(U3-PC4(ADC4{slash}SDA)-Pad27)") (class "Default")
      (node (ref "U3") (pin "27") (pinfunction "PC4(ADC4/SDA)_27") (pintype "bidirectional"))
    )
    (net (code "106") (name "unconnected-(U3-PC5(ADC5{slash}SCL)-Pad28)") (class "Default")
      (node (ref "U3") (pin "28") (pinfunction "PC5(ADC5/SCL)_28") (pintype "bidirectional"))
    )
    (net (code "107") (name "unconnected-(U4-CA1-Pad40)") (class "Default")
      (node (ref "U4") (pin "40") (pinfunction "CA1_40") (pintype "bidirectional"))
    )
    (net (code "108") (name "unconnected-(U4-CA2-Pad39)") (class "Default")
      (node (ref "U4") (pin "39") (pinfunction "CA2_39") (pintype "bidirectional"))
    )
    (net (code "109") (name "unconnected-(U4-CB1-Pad18)") (class "Default")
      (node (ref "U4") (pin "18") (pinfunction "CB1_18") (pintype "bidirectional"))
    )
    (net (code "110") (name "unconnected-(U4-CB2-Pad19)") (class "Default")
      (node (ref "U4") (pin "19") (pinfunction "CB2_19") (pintype "bidirectional"))
    )
    (net (code "111") (name "unconnected-(U4-PA0-Pad2)") (class "Default")
      (node (ref "U4") (pin "2") (pinfunction "PA0_2") (pintype "bidirectional"))
    )
    (net (code "112") (name "unconnected-(U4-PA1-Pad3)") (class "Default")
      (node (ref "U4") (pin "3") (pinfunction "PA1_3") (pintype "bidirectional"))
    )
    (net (code "113") (name "unconnected-(U4-PA2-Pad4)") (class "Default")
      (node (ref "U4") (pin "4") (pinfunction "PA2_4") (pintype "bidirectional"))
    )
    (net (code "114") (name "unconnected-(U4-PA3-Pad5)") (class "Default")
      (node (ref "U4") (pin "5") (pinfunction "PA3_5") (pintype "bidirectional"))
    )
    (net (code "115") (name "unconnected-(U4-PA4-Pad6)") (class "Default")
      (node (ref "U4") (pin "6") (pinfunction "PA4_6") (pintype "bidirectional"))
    )
    (net (code "116") (name "unconnected-(U4-PA5-Pad7)") (class "Default")
      (node (ref "U4") (pin "7") (pinfunction "PA5_7") (pintype "bidirectional"))
    )
    (net (code "117") (name "unconnected-(U4-PA6-Pad8)") (class "Default")
      (node (ref "U4") (pin "8") (pinfunction "PA6_8") (pintype "bidirectional"))
    )
    (net (code "118") (name "unconnected-(U4-PA7-Pad9)") (class "Default")
      (node (ref "U4") (pin "9") (pinfunction "PA7_9") (pintype "bidirectional"))
    )
    (net (code "119") (name "unconnected-(U4-PB0-Pad10)") (class "Default")
      (node (ref "U4") (pin "10") (pinfunction "PB0_10") (pintype "bidirectional"))
    )
    (net (code "120") (name "unconnected-(U4-PB1-Pad11)") (class "Default")
      (node (ref "U4") (pin "11") (pinfunction "PB1_11") (pintype "bidirectional"))
    )
    (net (code "121") (name "unconnected-(U4-PB2-Pad12)") (class "Default")
      (node (ref "U4") (pin "12") (pinfunction "PB2_12") (pintype "bidirectional"))
    )
    (net (code "122") (name "unconnected-(U4-PB3-Pad13)") (class "Default")
      (node (ref "U4") (pin "13") (pinfunction "PB3_13") (pintype "bidirectional"))
    )
    (net (code "123") (name "unconnected-(U4-PB4-Pad14)") (class "Default")
      (node (ref "U4") (pin "14") (pinfunction "PB4_14") (pintype "bidirectional"))
    )
    (net (code "124") (name "unconnected-(U4-PB5-Pad15)") (class "Default")
      (node (ref "U4") (pin "15") (pinfunction "PB5_15") (pintype "bidirectional"))
    )
    (net (code "125") (name "unconnected-(U4-PB6-Pad16)") (class "Default")
      (node (ref "U4") (pin "16") (pinfunction "PB6_16") (pintype "bidirectional"))
    )
    (net (code "126") (name "unconnected-(U4-PB7-Pad17)") (class "Default")
      (node (ref "U4") (pin "17") (pinfunction "PB7_17") (pintype "bidirectional"))
    )
    (net (code "127") (name "unconnected-(U6-RTS-Pad3)") (class "Default")
      (node (ref "U6") (pin "3") (pinfunction "RTS_3") (pintype "bidirectional"))
    )
    (net (code "128") (name "unconnected-(U6-VCC-Pad4)") (class "Default")
      (node (ref "U6") (pin "4") (pinfunction "VCC_4") (pintype "bidirectional"))
    )
    (net (code "129") (name "unconnected-(X1-Pad2)") (class "Default")
      (node (ref "X1") (pin "2") (pinfunction "2_2") (pintype "passive"))
    )
    (net (code "130") (name "unconnected-(X1-Pad8)") (class "Default")
      (node (ref "X1") (pin "8") (pinfunction "8_8") (pintype "passive"))
    )
  )
)
